# LED_strips.net
KiCad netlist of a schematic drawn in Altium Designer
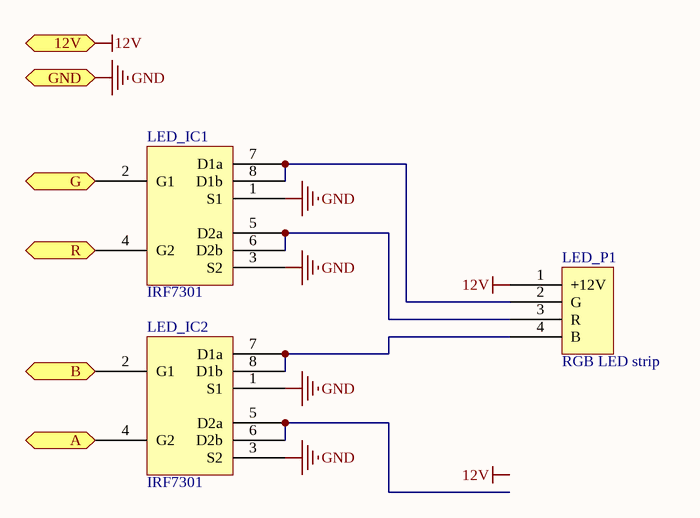
[diagram p0: LED strips.SchDoc]

(export (version "E")
  (design (tool "Eeschema 10.0.6"))
  (components
    (comp (ref "LED_IC1")
      (value "IRF7301")
      (footprint "SOIC8")
      (libsource (lib "Core51822-related") (part "IRF7301"))
    )
    (comp (ref "LED_IC2")
      (value "IRF7301")
      (footprint "SOIC8")
      (libsource (lib "Core51822-related") (part "IRF7301"))
    )
    (comp (ref "LED_P1")
      (value "RGB LED strip")
      (footprint "LED strip RGB connector")
      (libsource (lib "Core51822-related") (part "RGB LED strip"))
    )
  )
  (nets
    (net (code "1") (name "/A") (class "Default")
      (node (ref "LED_IC2") (pin "4") (pinfunction "G2_4") (pintype "passive"))
    )
    (net (code "2") (name "/B") (class "Default")
      (node (ref "LED_IC2") (pin "2") (pinfunction "G1_2") (pintype "passive"))
    )
    (net (code "3") (name "/G") (class "Default")
      (node (ref "LED_IC1") (pin "2") (pinfunction "G1_2") (pintype "passive"))
    )
    (net (code "4") (name "/R") (class "Default")
      (node (ref "LED_IC1") (pin "4") (pinfunction "G2_4") (pintype "passive"))
    )
    (net (code "5") (name "12V") (class "Default")
      (node (ref "LED_P1") (pin "1") (pinfunction "+12V_1") (pintype "passive"))
    )
    (net (code "6") (name "GND") (class "Default")
      (node (ref "LED_IC1") (pin "1") (pinfunction "S1_1") (pintype "passive"))
      (node (ref "LED_IC1") (pin "3") (pinfunction "S2_3") (pintype "passive"))
      (node (ref "LED_IC2") (pin "1") (pinfunction "S1_1") (pintype "passive"))
      (node (ref "LED_IC2") (pin "3") (pinfunction "S2_3") (pintype "passive"))
    )
    (net (code "7") (name "Net-(LED_IC1-D1a)") (class "Default")
      (node (ref "LED_IC1") (pin "7") (pinfunction "D1a_7") (pintype "passive"))
      (node (ref "LED_IC1") (pin "8") (pinfunction "D1b_8") (pintype "passive"))
      (node (ref "LED_P1") (pin "2") (pinfunction "G_2") (pintype "passive"))
    )
    (net (code "8") (name "Net-(LED_IC1-D2a)") (class "Default")
      (node (ref "LED_IC1") (pin "5") (pinfunction "D2a_5") (pintype "passive"))
      (node (ref "LED_IC1") (pin "6") (pinfunction "D2b_6") (pintype "passive"))
      (node (ref "LED_P1") (pin "3") (pinfunction "R_3") (pintype "passive"))
    )
    (net (code "9") (name "Net-(LED_IC2-D1a)") (class "Default")
      (node (ref "LED_IC2") (pin "7") (pinfunction "D1a_7") (pintype "passive"))
      (node (ref "LED_IC2") (pin "8") (pinfunction "D1b_8") (pintype "passive"))
      (node (ref "LED_P1") (pin "4") (pinfunction "B_4") (pintype "passive"))
    )
    (net (code "10") (name "Net-(LED_IC2-D2a)") (class "Default")
      (node (ref "LED_IC2") (pin "5") (pinfunction "D2a_5") (pintype "passive"))
      (node (ref "LED_IC2") (pin "6") (pinfunction "D2b_6") (pintype "passive"))
    )
  )
)
